# PulseFit.net
KiCad netlist of a schematic drawn in EAGLE
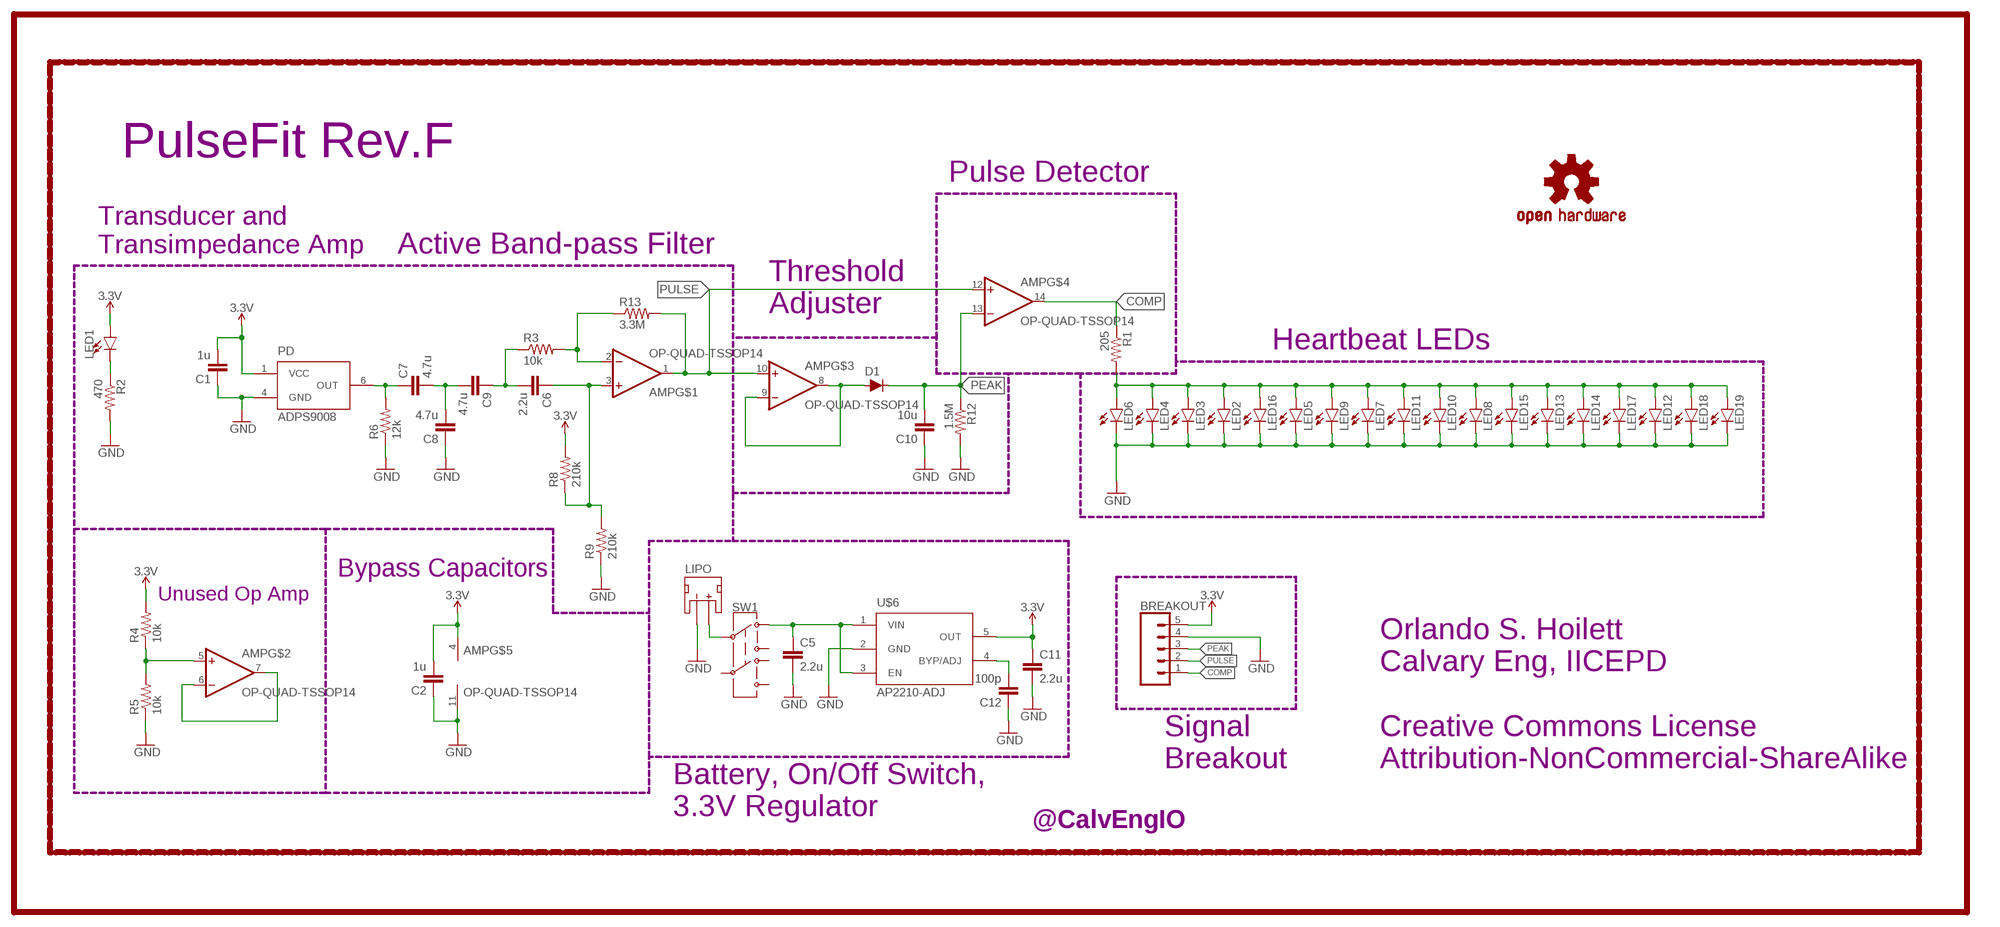
[diagram p0: schematic, sheet 1]

(export (version "E")
  (design (tool "Eeschema 10.0.6"))
  (components
    (comp (ref "AMP")
      (value "OP-QUAD-TSSOP14")
      (footprint "eagle-import:TSSOP14")
      (libsource (lib "eagle-import") (part "OP-QUAD-TSSOP14"))
    )
    (comp (ref "BREAKOUT")
      (value "CONN_05")
      (footprint "eagle-import:1X05")
      (libsource (lib "eagle-import") (part "CONN_05"))
    )
    (comp (ref "C1")
      (value "1u")
      (footprint "eagle-import:C0402")
      (libsource (lib "eagle-import") (part "CAPACITOR0402"))
    )
    (comp (ref "C2")
      (value "1u")
      (footprint "eagle-import:C0402")
      (libsource (lib "eagle-import") (part "CAPACITOR0402"))
    )
    (comp (ref "C5")
      (value "2.2u")
      (footprint "eagle-import:C0603")
      (libsource (lib "eagle-import") (part "CAPACITOR0603"))
    )
    (comp (ref "C6")
      (value "2.2u")
      (footprint "eagle-import:C0603")
      (libsource (lib "eagle-import") (part "CAPACITOR0603"))
    )
    (comp (ref "C7")
      (value "4.7u")
      (footprint "eagle-import:C0603")
      (libsource (lib "eagle-import") (part "CAPACITOR0603"))
    )
    (comp (ref "C8")
      (value "4.7u")
      (footprint "eagle-import:C0603")
      (libsource (lib "eagle-import") (part "CAPACITOR0603"))
    )
    (comp (ref "C9")
      (value "4.7u")
      (footprint "eagle-import:C0603")
      (libsource (lib "eagle-import") (part "CAPACITOR0603"))
    )
    (comp (ref "C10")
      (value "10u")
      (footprint "eagle-import:C0805")
      (libsource (lib "eagle-import") (part "CAPACITOR0805"))
    )
    (comp (ref "C11")
      (value "2.2u")
      (footprint "eagle-import:C0603")
      (libsource (lib "eagle-import") (part "CAPACITOR0603"))
    )
    (comp (ref "C12")
      (value "100p")
      (footprint "eagle-import:C0402")
      (libsource (lib "eagle-import") (part "CAPACITOR0402"))
    )
    (comp (ref "D1")
      (value "DIODE-BAS16J")
      (footprint "eagle-import:SOD-323")
      (libsource (lib "eagle-import") (part "DIODE-BAS16J"))
    )
    (comp (ref "LED1")
      (value "LEDZ-BEND")
      (footprint "eagle-import:2-SMD.Z-BEND")
      (libsource (lib "eagle-import") (part "LEDZ-BEND"))
    )
    (comp (ref "LED2")
      (value "LED5MM")
      (footprint "eagle-import:LED5MM")
      (libsource (lib "eagle-import") (part "SparkFun-LED_LED5MM"))
    )
    (comp (ref "LED3")
      (value "LED5MM")
      (footprint "eagle-import:LED5MM")
      (libsource (lib "eagle-import") (part "SparkFun-LED_LED5MM"))
    )
    (comp (ref "LED4")
      (value "LED5MM")
      (footprint "eagle-import:LED5MM")
      (libsource (lib "eagle-import") (part "SparkFun-LED_LED5MM"))
    )
    (comp (ref "LED5")
      (value "LED5MM")
      (footprint "eagle-import:LED5MM")
      (libsource (lib "eagle-import") (part "SparkFun-LED_LED5MM"))
    )
    (comp (ref "LED6")
      (value "LED5MM")
      (footprint "eagle-import:LED5MM")
      (libsource (lib "eagle-import") (part "SparkFun-LED_LED5MM"))
    )
    (comp (ref "LED7")
      (value "LED5MM")
      (footprint "eagle-import:LED5MM")
      (libsource (lib "eagle-import") (part "SparkFun-LED_LED5MM"))
    )
    (comp (ref "LED8")
      (value "LED5MM")
      (footprint "eagle-import:LED5MM")
      (libsource (lib "eagle-import") (part "SparkFun-LED_LED5MM"))
    )
    (comp (ref "LED9")
      (value "LED5MM")
      (footprint "eagle-import:LED5MM")
      (libsource (lib "eagle-import") (part "SparkFun-LED_LED5MM"))
    )
    (comp (ref "LED10")
      (value "LED5MM")
      (footprint "eagle-import:LED5MM")
      (libsource (lib "eagle-import") (part "SparkFun-LED_LED5MM"))
    )
    (comp (ref "LED11")
      (value "LED5MM")
      (footprint "eagle-import:LED5MM")
      (libsource (lib "eagle-import") (part "SparkFun-LED_LED5MM"))
    )
    (comp (ref "LED12")
      (value "LED5MM")
      (footprint "eagle-import:LED5MM")
      (libsource (lib "eagle-import") (part "SparkFun-LED_LED5MM"))
    )
    (comp (ref "LED13")
      (value "LED5MM")
      (footprint "eagle-import:LED5MM")
      (libsource (lib "eagle-import") (part "SparkFun-LED_LED5MM"))
    )
    (comp (ref "LED14")
      (value "LED5MM")
      (footprint "eagle-import:LED5MM")
      (libsource (lib "eagle-import") (part "SparkFun-LED_LED5MM"))
    )
    (comp (ref "LED15")
      (value "LED5MM")
      (footprint "eagle-import:LED5MM")
      (libsource (lib "eagle-import") (part "SparkFun-LED_LED5MM"))
    )
    (comp (ref "LED16")
      (value "LED5MM")
      (footprint "eagle-import:LED5MM")
      (libsource (lib "eagle-import") (part "SparkFun-LED_LED5MM"))
    )
    (comp (ref "LED17")
      (value "LED5MM")
      (footprint "eagle-import:LED5MM")
      (libsource (lib "eagle-import") (part "SparkFun-LED_LED5MM"))
    )
    (comp (ref "LED18")
      (value "LED5MM")
      (footprint "eagle-import:LED5MM")
      (libsource (lib "eagle-import") (part "SparkFun-LED_LED5MM"))
    )
    (comp (ref "LED19")
      (value "LED5MM")
      (footprint "eagle-import:LED5MM")
      (libsource (lib "eagle-import") (part "SparkFun-LED_LED5MM"))
    )
    (comp (ref "LIPO")
      (value "JST_2MM_MALE")
      (footprint "eagle-import:JST-2-SMD")
      (libsource (lib "eagle-import") (part "JST_2MM_MALE"))
    )
    (comp (ref "LOGO1")
      (value "OSHW-LOGOS")
      (footprint "eagle-import:OSHW-LOGO-S")
      (libsource (lib "eagle-import") (part "OSHW-LOGOS"))
    )
    (comp (ref "PD")
      (value "ADPS9008")
      (footprint "eagle-import:6-PIN.CHIPLED")
      (libsource (lib "eagle-import") (part "ADPS9008"))
    )
    (comp (ref "R1")
      (value "205")
      (footprint "eagle-import:R0402")
      (libsource (lib "eagle-import") (part "RESISTOR0402"))
    )
    (comp (ref "R2")
      (value "470")
      (footprint "eagle-import:R0402")
      (libsource (lib "eagle-import") (part "RESISTOR0402"))
    )
    (comp (ref "R3")
      (value "10k")
      (footprint "eagle-import:R0402")
      (libsource (lib "eagle-import") (part "RESISTOR0402"))
    )
    (comp (ref "R4")
      (value "10k")
      (footprint "eagle-import:R0402")
      (libsource (lib "eagle-import") (part "RESISTOR0402"))
    )
    (comp (ref "R5")
      (value "10k")
      (footprint "eagle-import:R0402")
      (libsource (lib "eagle-import") (part "RESISTOR0402"))
    )
    (comp (ref "R6")
      (value "12k")
      (footprint "eagle-import:R0402")
      (libsource (lib "eagle-import") (part "RESISTOR0402"))
    )
    (comp (ref "R8")
      (value "210k")
      (footprint "eagle-import:R0402")
      (libsource (lib "eagle-import") (part "RESISTOR0402"))
    )
    (comp (ref "R9")
      (value "210k")
      (footprint "eagle-import:R0402")
      (libsource (lib "eagle-import") (part "RESISTOR0402"))
    )
    (comp (ref "R12")
      (value "1.5M")
      (footprint "eagle-import:R0402")
      (libsource (lib "eagle-import") (part "RESISTOR0402"))
    )
    (comp (ref "R13")
      (value "3.3M")
      (footprint "eagle-import:R0402")
      (libsource (lib "eagle-import") (part "RESISTOR0402"))
    )
    (comp (ref "SW1")
      (value "SWITCH.JS202011JCQN")
      (footprint "eagle-import:SWITCH.00")
      (libsource (lib "eagle-import") (part "SWITCH.JS202011JCQN"))
    )
    (comp (ref "U$1")
      (value "CALVENGIO_HANDLEHANDLE.08")
      (footprint "eagle-import:CALVENGIO_HANDLE.08")
      (libsource (lib "eagle-import") (part "CALVENGIO_HANDLEHANDLE.08"))
    )
    (comp (ref "U$6")
      (value "AP2210-ADJ")
      (footprint "eagle-import:SOT23-5")
      (libsource (lib "eagle-import") (part "AP2210-ADJ"))
    )
  )
  (nets
    (net (code "1") (name "3.3V") (class "Default")
      (node (ref "AMP") (pin "4") (pinfunction "V+_4") (pintype "power_in"))
      (node (ref "BREAKOUT") (pin "5") (pinfunction "5_5") (pintype "passive"))
      (node (ref "C1") (pin "2") (pinfunction "2_2") (pintype "passive"))
      (node (ref "C11") (pin "1") (pinfunction "1_1") (pintype "passive"))
      (node (ref "C2") (pin "2") (pinfunction "2_2") (pintype "passive"))
      (node (ref "LED1") (pin "+") (pinfunction "A_+") (pintype "passive"))
      (node (ref "PD") (pin "1") (pinfunction "VCC_1") (pintype "bidirectional"))
      (node (ref "R4") (pin "2") (pinfunction "2_2") (pintype "passive"))
      (node (ref "R8") (pin "2") (pinfunction "2_2") (pintype "passive"))
      (node (ref "U$6") (pin "5") (pinfunction "OUT_5") (pintype "bidirectional"))
    )
    (net (code "2") (name "COMP") (class "Default")
      (node (ref "AMP") (pin "14") (pinfunction "OUT_14") (pintype "output"))
      (node (ref "BREAKOUT") (pin "1") (pinfunction "1_1") (pintype "passive"))
      (node (ref "R1") (pin "1") (pinfunction "1_1") (pintype "passive"))
    )
    (net (code "3") (name "GND") (class "Default")
      (node (ref "AMP") (pin "11") (pinfunction "V-_11") (pintype "power_in"))
      (node (ref "BREAKOUT") (pin "4") (pinfunction "4_4") (pintype "passive"))
      (node (ref "C1") (pin "1") (pinfunction "1_1") (pintype "passive"))
      (node (ref "C10") (pin "1") (pinfunction "1_1") (pintype "passive"))
      (node (ref "C11") (pin "2") (pinfunction "2_2") (pintype "passive"))
      (node (ref "C12") (pin "1") (pinfunction "1_1") (pintype "passive"))
      (node (ref "C2") (pin "1") (pinfunction "1_1") (pintype "passive"))
      (node (ref "C5") (pin "2") (pinfunction "2_2") (pintype "passive"))
      (node (ref "C8") (pin "1") (pinfunction "1_1") (pintype "passive"))
      (node (ref "LED10") (pin "K") (pinfunction "C_K") (pintype "passive"))
      (node (ref "LED11") (pin "K") (pinfunction "C_K") (pintype "passive"))
      (node (ref "LED12") (pin "K") (pinfunction "C_K") (pintype "passive"))
      (node (ref "LED13") (pin "K") (pinfunction "C_K") (pintype "passive"))
      (node (ref "LED14") (pin "K") (pinfunction "C_K") (pintype "passive"))
      (node (ref "LED15") (pin "K") (pinfunction "C_K") (pintype "passive"))
      (node (ref "LED16") (pin "K") (pinfunction "C_K") (pintype "passive"))
      (node (ref "LED17") (pin "K") (pinfunction "C_K") (pintype "passive"))
      (node (ref "LED18") (pin "K") (pinfunction "C_K") (pintype "passive"))
      (node (ref "LED19") (pin "K") (pinfunction "C_K") (pintype "passive"))
      (node (ref "LED2") (pin "K") (pinfunction "C_K") (pintype "passive"))
      (node (ref "LED3") (pin "K") (pinfunction "C_K") (pintype "passive"))
      (node (ref "LED4") (pin "K") (pinfunction "C_K") (pintype "passive"))
      (node (ref "LED5") (pin "K") (pinfunction "C_K") (pintype "passive"))
      (node (ref "LED6") (pin "K") (pinfunction "C_K") (pintype "passive"))
      (node (ref "LED7") (pin "K") (pinfunction "C_K") (pintype "passive"))
      (node (ref "LED8") (pin "K") (pinfunction "C_K") (pintype "passive"))
      (node (ref "LED9") (pin "K") (pinfunction "C_K") (pintype "passive"))
      (node (ref "LIPO") (pin "1") (pinfunction "-_1") (pintype "bidirectional"))
      (node (ref "PD") (pin "4") (pinfunction "GND_4") (pintype "bidirectional"))
      (node (ref "R12") (pin "2") (pinfunction "2_2") (pintype "passive"))
      (node (ref "R2") (pin "2") (pinfunction "2_2") (pintype "passive"))
      (node (ref "R5") (pin "1") (pinfunction "1_1") (pintype "passive"))
      (node (ref "R6") (pin "1") (pinfunction "1_1") (pintype "passive"))
      (node (ref "R9") (pin "1") (pinfunction "1_1") (pintype "passive"))
      (node (ref "U$6") (pin "2") (pinfunction "GND_2") (pintype "bidirectional"))
    )
    (net (code "4") (name "Net-(AMPA-+IN)") (class "Default")
      (node (ref "AMP") (pin "3") (pinfunction "+IN_3") (pintype "input"))
      (node (ref "C6") (pin "1") (pinfunction "1_1") (pintype "passive"))
      (node (ref "R8") (pin "1") (pinfunction "1_1") (pintype "passive"))
      (node (ref "R9") (pin "2") (pinfunction "2_2") (pintype "passive"))
    )
    (net (code "5") (name "Net-(AMPA--IN)") (class "Default")
      (node (ref "AMP") (pin "2") (pinfunction "-IN_2") (pintype "input"))
      (node (ref "R13") (pin "1") (pinfunction "1_1") (pintype "passive"))
      (node (ref "R3") (pin "2") (pinfunction "2_2") (pintype "passive"))
    )
    (net (code "6") (name "Net-(AMPB-+IN)") (class "Default")
      (node (ref "AMP") (pin "5") (pinfunction "+IN_5") (pintype "input"))
      (node (ref "R4") (pin "1") (pinfunction "1_1") (pintype "passive"))
      (node (ref "R5") (pin "2") (pinfunction "2_2") (pintype "passive"))
    )
    (net (code "7") (name "Net-(AMPB--IN)") (class "Default")
      (node (ref "AMP") (pin "6") (pinfunction "-IN_6") (pintype "input"))
      (node (ref "AMP") (pin "7") (pinfunction "OUT_7") (pintype "output"))
    )
    (net (code "8") (name "Net-(AMPC--IN)") (class "Default")
      (node (ref "AMP") (pin "8") (pinfunction "OUT_8") (pintype "output"))
      (node (ref "AMP") (pin "9") (pinfunction "-IN_9") (pintype "input"))
      (node (ref "D1") (pin "A") (pinfunction "A_A") (pintype "passive"))
    )
    (net (code "9") (name "Net-(C6-Pad2)") (class "Default")
      (node (ref "C6") (pin "2") (pinfunction "2_2") (pintype "passive"))
      (node (ref "C9") (pin "1") (pinfunction "1_1") (pintype "passive"))
      (node (ref "R3") (pin "1") (pinfunction "1_1") (pintype "passive"))
    )
    (net (code "10") (name "Net-(C7-Pad2)") (class "Default")
      (node (ref "C7") (pin "2") (pinfunction "2_2") (pintype "passive"))
      (node (ref "C8") (pin "2") (pinfunction "2_2") (pintype "passive"))
      (node (ref "C9") (pin "2") (pinfunction "2_2") (pintype "passive"))
    )
    (net (code "11") (name "Net-(LED1-C)") (class "Default")
      (node (ref "LED1") (pin "-") (pinfunction "C_-") (pintype "passive"))
      (node (ref "R2") (pin "1") (pinfunction "1_1") (pintype "passive"))
    )
    (net (code "12") (name "Net-(LED10-PadA)") (class "Default")
      (node (ref "LED10") (pin "A") (pinfunction "A_A") (pintype "passive"))
      (node (ref "LED11") (pin "A") (pinfunction "A_A") (pintype "passive"))
      (node (ref "LED12") (pin "A") (pinfunction "A_A") (pintype "passive"))
      (node (ref "LED13") (pin "A") (pinfunction "A_A") (pintype "passive"))
      (node (ref "LED14") (pin "A") (pinfunction "A_A") (pintype "passive"))
      (node (ref "LED15") (pin "A") (pinfunction "A_A") (pintype "passive"))
      (node (ref "LED16") (pin "A") (pinfunction "A_A") (pintype "passive"))
      (node (ref "LED17") (pin "A") (pinfunction "A_A") (pintype "passive"))
      (node (ref "LED18") (pin "A") (pinfunction "A_A") (pintype "passive"))
      (node (ref "LED19") (pin "A") (pinfunction "A_A") (pintype "passive"))
      (node (ref "LED2") (pin "A") (pinfunction "A_A") (pintype "passive"))
      (node (ref "LED3") (pin "A") (pinfunction "A_A") (pintype "passive"))
      (node (ref "LED4") (pin "A") (pinfunction "A_A") (pintype "passive"))
      (node (ref "LED5") (pin "A") (pinfunction "A_A") (pintype "passive"))
      (node (ref "LED6") (pin "A") (pinfunction "A_A") (pintype "passive"))
      (node (ref "LED7") (pin "A") (pinfunction "A_A") (pintype "passive"))
      (node (ref "LED8") (pin "A") (pinfunction "A_A") (pintype "passive"))
      (node (ref "LED9") (pin "A") (pinfunction "A_A") (pintype "passive"))
      (node (ref "R1") (pin "2") (pinfunction "2_2") (pintype "passive"))
    )
    (net (code "13") (name "Net-(LIPO-+)") (class "Default")
      (node (ref "LIPO") (pin "2") (pinfunction "+_2") (pintype "bidirectional"))
      (node (ref "SW1") (pin "2") (pinfunction "2_2") (pintype "bidirectional"))
    )
    (net (code "14") (name "Net-(PD-OUT)") (class "Default")
      (node (ref "C7") (pin "1") (pinfunction "1_1") (pintype "passive"))
      (node (ref "PD") (pin "6") (pinfunction "OUT_6") (pintype "bidirectional"))
      (node (ref "R6") (pin "2") (pinfunction "2_2") (pintype "passive"))
    )
    (net (code "15") (name "Net-(U$6-BYP{slash}ADJ)") (class "Default")
      (node (ref "C12") (pin "2") (pinfunction "2_2") (pintype "passive"))
      (node (ref "U$6") (pin "4") (pinfunction "BYP/ADJ_4") (pintype "bidirectional"))
    )
    (net (code "16") (name "Net-(U$6-EN)") (class "Default")
      (node (ref "C5") (pin "1") (pinfunction "1_1") (pintype "passive"))
      (node (ref "SW1") (pin "1") (pinfunction "1_1") (pintype "bidirectional"))
      (node (ref "U$6") (pin "1") (pinfunction "VIN_1") (pintype "bidirectional"))
      (node (ref "U$6") (pin "3") (pinfunction "EN_3") (pintype "bidirectional"))
    )
    (net (code "17") (name "PEAK") (class "Default")
      (node (ref "AMP") (pin "13") (pinfunction "-IN_13") (pintype "input"))
      (node (ref "BREAKOUT") (pin "3") (pinfunction "3_3") (pintype "passive"))
      (node (ref "C10") (pin "2") (pinfunction "2_2") (pintype "passive"))
      (node (ref "D1") (pin "C") (pinfunction "C_C") (pintype "passive"))
      (node (ref "R12") (pin "1") (pinfunction "1_1") (pintype "passive"))
    )
    (net (code "18") (name "PULSE") (class "Default")
      (node (ref "AMP") (pin "1") (pinfunction "OUT_1") (pintype "output"))
      (node (ref "AMP") (pin "10") (pinfunction "+IN_10") (pintype "input"))
      (node (ref "AMP") (pin "12") (pinfunction "+IN_12") (pintype "input"))
      (node (ref "BREAKOUT") (pin "2") (pinfunction "2_2") (pintype "passive"))
      (node (ref "R13") (pin "2") (pinfunction "2_2") (pintype "passive"))
    )
    (net (code "19") (name "unconnected-(LIPO-PAD1-PadNC1)") (class "Default")
      (node (ref "LIPO") (pin "NC1") (pinfunction "PAD1_NC1") (pintype "bidirectional"))
    )
    (net (code "20") (name "unconnected-(LIPO-PAD2-PadNC2)") (class "Default")
      (node (ref "LIPO") (pin "NC2") (pinfunction "PAD2_NC2") (pintype "bidirectional"))
    )
    (net (code "21") (name "unconnected-(SW1-Pad3)") (class "Default")
      (node (ref "SW1") (pin "3") (pinfunction "3_3") (pintype "bidirectional"))
    )
    (net (code "22") (name "unconnected-(SW1-Pad5)") (class "Default")
      (node (ref "SW1") (pin "5") (pinfunction "5_5") (pintype "bidirectional"))
    )
    (net (code "23") (name "unconnected-(SW1-Pad6)") (class "Default")
      (node (ref "SW1") (pin "6") (pinfunction "6_6") (pintype "bidirectional"))
    )
    (net (code "24") (name "unconnected-(SW1-Pad7)") (class "Default")
      (node (ref "SW1") (pin "7") (pinfunction "7_7") (pintype "bidirectional"))
    )
  )
)
